# DCDCDC-R2.net
KiCad netlist of a schematic drawn in EAGLE
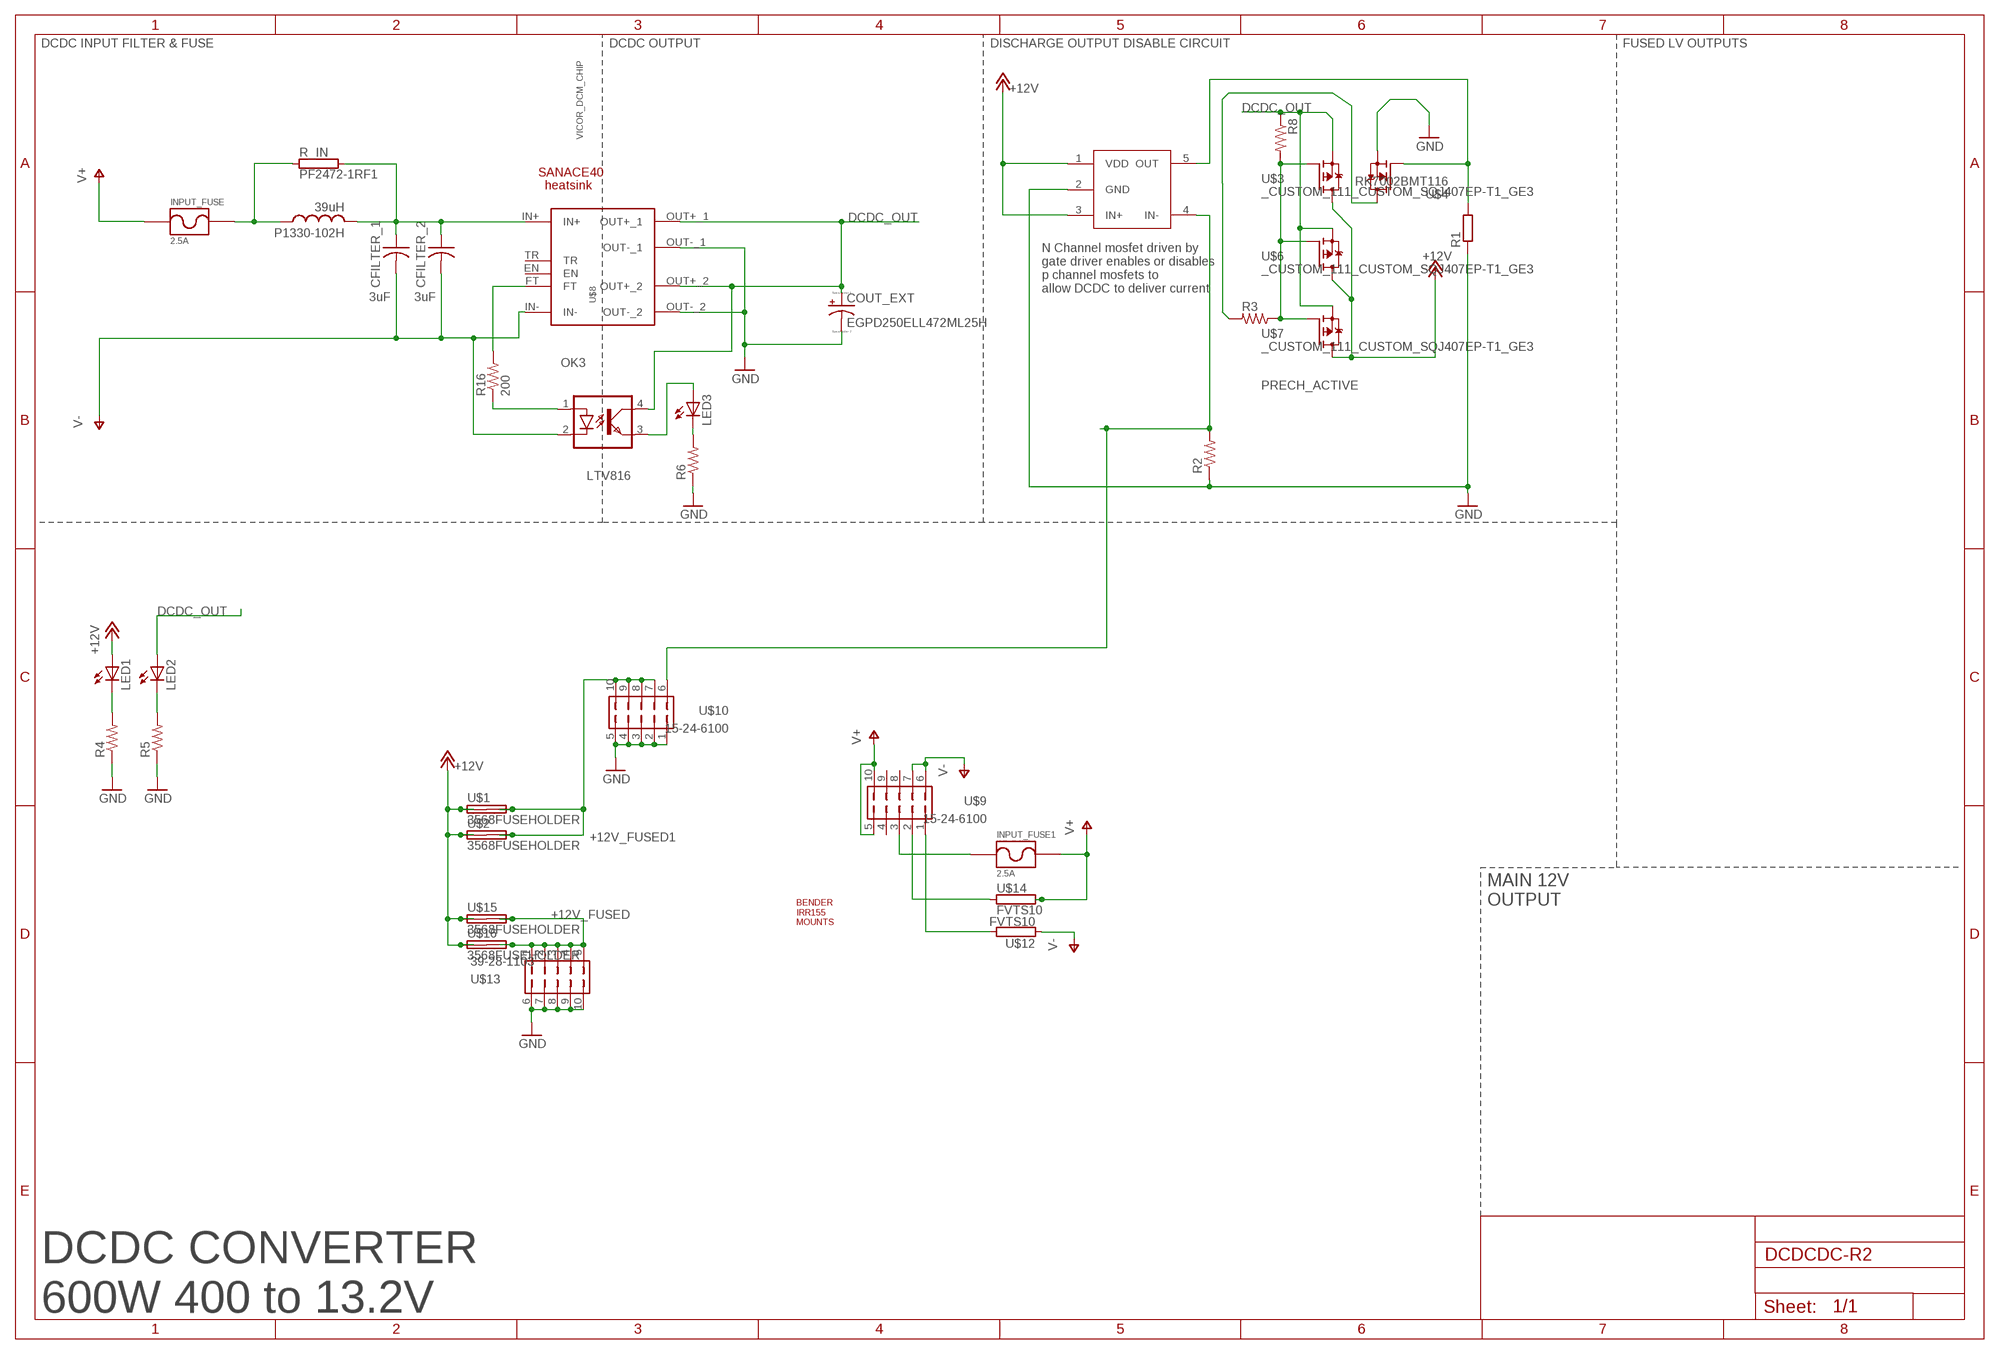
[diagram p0: schematic, sheet 1]

(export (version "E")
  (design (tool "Eeschema 10.0.6"))
  (components
    (comp (ref "CFILTER_1")
      (value "3uF")
      (footprint "eagle-import:CERALINK_FA3")
      (libsource (lib "eagle-import") (part "B58035U5305M062"))
    )
    (comp (ref "CFILTER_2")
      (value "3uF")
      (footprint "eagle-import:CERALINK_FA3")
      (libsource (lib "eagle-import") (part "B58035U5305M062"))
    )
    (comp (ref "COUT_EXT")
      (value "EGPD250ELL472ML25H")
      (footprint "eagle-import:E7,5-16")
      (libsource (lib "eagle-import") (part "CPOL-USE7.5-16"))
    )
    (comp (ref "INPUT_FUSE")
      (value "2.5A")
      (footprint "eagle-import:_CUSTOM_PARTS_LF_885")
      (libsource (lib "eagle-import") (part "_CUSTOM_PARTS_LF_885"))
    )
    (comp (ref "INPUT_FUSE1")
      (value "2.5A")
      (footprint "eagle-import:_CUSTOM_PARTS_LF_885")
      (libsource (lib "eagle-import") (part "_CUSTOM_PARTS_LF_885"))
    )
    (comp (ref "LED1")
      (value "LED3MM")
      (footprint "eagle-import:LED3MM")
      (libsource (lib "eagle-import") (part "LED3MM"))
    )
    (comp (ref "LED2")
      (value "LED3MM")
      (footprint "eagle-import:LED3MM")
      (libsource (lib "eagle-import") (part "LED3MM"))
    )
    (comp (ref "LED3")
      (value "LED3MM")
      (footprint "eagle-import:LED3MM")
      (libsource (lib "eagle-import") (part "LED3MM"))
    )
    (comp (ref "OK3")
      (value "LTV816")
      (footprint "eagle-import:DIL04")
      (libsource (lib "eagle-import") (part "LTV816"))
    )
    (comp (ref "P1330-102H")
      (value "39uH")
      (footprint "eagle-import:L_1510_NONSTANDARD")
      (libsource (lib "eagle-import") (part "SRP1770TA-390M"))
    )
    (comp (ref "R1")
      (value "R-EU_R0805")
      (footprint "eagle-import:R0805")
      (libsource (lib "eagle-import") (part "R-EU_R0805"))
    )
    (comp (ref "R2")
      (value "R-US_R0805")
      (footprint "eagle-import:R0805")
      (libsource (lib "eagle-import") (part "ACC-MB-R0_13324935_R-US_R0805"))
    )
    (comp (ref "R3")
      (value "R-US_R0805")
      (footprint "eagle-import:R0805")
      (libsource (lib "eagle-import") (part "ACC-MB-R0_13324935_R-US_R0805"))
    )
    (comp (ref "R4")
      (value "R-US_R0805")
      (footprint "eagle-import:R0805")
      (libsource (lib "eagle-import") (part "R-US_R0805"))
    )
    (comp (ref "R5")
      (value "R-US_R0805")
      (footprint "eagle-import:R0805")
      (libsource (lib "eagle-import") (part "R-US_R0805"))
    )
    (comp (ref "R6")
      (value "R-US_R0805")
      (footprint "eagle-import:R0805")
      (libsource (lib "eagle-import") (part "R-US_R0805"))
    )
    (comp (ref "R8")
      (value "R-US_R0805")
      (footprint "eagle-import:R0805")
      (libsource (lib "eagle-import") (part "ACC-MB-R0_13324935_R-US_R0805"))
    )
    (comp (ref "R16")
      (value "200")
      (footprint "eagle-import:R2010")
      (libsource (lib "eagle-import") (part "Main_14107900_R-US_R2010"))
    )
    (comp (ref "R_IN")
      (value "PF2472-1RF1")
      (footprint "eagle-import:TO-247-2V")
      (libsource (lib "eagle-import") (part "RMG100-V"))
    )
    (comp (ref "U$1")
      (value "3568FUSEHOLDER")
      (footprint "eagle-import:3568")
      (libsource (lib "eagle-import") (part "3568FUSEHOLDER"))
    )
    (comp (ref "U$2")
      (value "3568FUSEHOLDER")
      (footprint "eagle-import:3568")
      (libsource (lib "eagle-import") (part "3568FUSEHOLDER"))
    )
    (comp (ref "U$3")
      (value "_CUSTOM_111_CUSTOM_SQJ407EP-T1_GE3")
      (footprint "eagle-import:_CUSTOM_111_CUSTOM_TRANS_SIRA90DP-T1-GE3")
      (libsource (lib "eagle-import") (part "_CUSTOM_111_CUSTOM_SQJ407EP-T1_GE3"))
    )
    (comp (ref "U$4")
      (value "RK7002BMT116")
      (footprint "eagle-import:SOT23")
      (libsource (lib "eagle-import") (part "RK7002BMT116"))
    )
    (comp (ref "U$5")
      (value "UCC27511AQDBVRQ1")
      (footprint "eagle-import:SOT23-5L")
      (libsource (lib "eagle-import") (part "UCC27511AQDBVRQ1"))
    )
    (comp (ref "U$6")
      (value "_CUSTOM_111_CUSTOM_SQJ407EP-T1_GE3")
      (footprint "eagle-import:_CUSTOM_111_CUSTOM_TRANS_SIRA90DP-T1-GE3")
      (libsource (lib "eagle-import") (part "_CUSTOM_111_CUSTOM_SQJ407EP-T1_GE3"))
    )
    (comp (ref "U$7")
      (value "_CUSTOM_111_CUSTOM_SQJ407EP-T1_GE3")
      (footprint "eagle-import:_CUSTOM_111_CUSTOM_TRANS_SIRA90DP-T1-GE3")
      (libsource (lib "eagle-import") (part "_CUSTOM_111_CUSTOM_SQJ407EP-T1_GE3"))
    )
    (comp (ref "U$8")
      (value "VICOR_DCM_CHIP")
      (footprint "eagle-import:VICOR_CHIP_HEATSINK")
      (libsource (lib "eagle-import") (part "VICOR_DCM_CHIP"))
    )
    (comp (ref "U$9")
      (value "15-24-6100")
      (footprint "eagle-import:15-24-6100")
      (libsource (lib "eagle-import") (part "15-24-6100"))
    )
    (comp (ref "U$10")
      (value "15-24-6100")
      (footprint "eagle-import:15-24-6100")
      (libsource (lib "eagle-import") (part "15-24-6100"))
    )
    (comp (ref "U$11")
      (value "BENDER_IRR155")
      (footprint "eagle-import:BENDER_IRR155")
      (libsource (lib "eagle-import") (part "BENDER_IRR155"))
    )
    (comp (ref "U$12")
      (value "FVTS10")
      (footprint "eagle-import:FVTS10")
      (libsource (lib "eagle-import") (part "FVTS10"))
    )
    (comp (ref "U$13")
      (value "39-28-1103")
      (footprint "eagle-import:39-28-1103")
      (libsource (lib "eagle-import") (part "39-28-1103"))
    )
    (comp (ref "U$14")
      (value "FVTS10")
      (footprint "eagle-import:FVTS10")
      (libsource (lib "eagle-import") (part "FVTS10"))
    )
    (comp (ref "U$15")
      (value "3568FUSEHOLDER")
      (footprint "eagle-import:3568")
      (libsource (lib "eagle-import") (part "3568FUSEHOLDER"))
    )
    (comp (ref "U$16")
      (value "3568FUSEHOLDER")
      (footprint "eagle-import:3568")
      (libsource (lib "eagle-import") (part "3568FUSEHOLDER"))
    )
    (comp (ref "U$17")
      (value "VICOR_HEATSINK_19MMLONG")
      (footprint "eagle-import:VICOR_HEATSINK_19MM_LONG")
      (libsource (lib "eagle-import") (part "VICOR_HEATSINK_19MMLONG"))
    )
    (comp (ref "U$18")
      (value "SANACE40")
      (footprint "eagle-import:SANACE40")
      (libsource (lib "eagle-import") (part "SANACE40"))
    )
  )
  (nets
    (net (code "1") (name "+12V") (class "Default")
      (node (ref "LED1") (pin "A") (pinfunction "A_A") (pintype "passive"))
      (node (ref "U$1") (pin "L1") (pinfunction "1A_L1") (pintype "passive"))
      (node (ref "U$1") (pin "L2") (pinfunction "1B_L2") (pintype "passive"))
      (node (ref "U$15") (pin "L1") (pinfunction "1A_L1") (pintype "passive"))
      (node (ref "U$15") (pin "L2") (pinfunction "1B_L2") (pintype "passive"))
      (node (ref "U$16") (pin "L1") (pinfunction "1A_L1") (pintype "passive"))
      (node (ref "U$16") (pin "L2") (pinfunction "1B_L2") (pintype "passive"))
      (node (ref "U$2") (pin "L1") (pinfunction "1A_L1") (pintype "passive"))
      (node (ref "U$2") (pin "L2") (pinfunction "1B_L2") (pintype "passive"))
      (node (ref "U$3") (pin "5") (pinfunction "D_5") (pintype "passive"))
      (node (ref "U$5") (pin "1") (pinfunction "VDD_1") (pintype "bidirectional"))
      (node (ref "U$5") (pin "3") (pinfunction "IN+_3") (pintype "bidirectional"))
      (node (ref "U$6") (pin "5") (pinfunction "D_5") (pintype "passive"))
      (node (ref "U$7") (pin "5") (pinfunction "D_5") (pintype "passive"))
    )
    (net (code "2") (name "/+12V_FUSED") (class "Default")
      (node (ref "U$13") (pin "1") (pinfunction "1_1") (pintype "passive"))
      (node (ref "U$13") (pin "2") (pinfunction "2_2") (pintype "passive"))
      (node (ref "U$13") (pin "3") (pinfunction "3_3") (pintype "passive"))
      (node (ref "U$13") (pin "4") (pinfunction "4_4") (pintype "passive"))
      (node (ref "U$13") (pin "5") (pinfunction "5_5") (pintype "passive"))
      (node (ref "U$15") (pin "R1") (pinfunction "2A_R1") (pintype "passive"))
      (node (ref "U$15") (pin "R2") (pinfunction "2B_R2") (pintype "passive"))
      (node (ref "U$16") (pin "R1") (pinfunction "2A_R1") (pintype "passive"))
      (node (ref "U$16") (pin "R2") (pinfunction "2B_R2") (pintype "passive"))
    )
    (net (code "3") (name "/+12V_FUSED1") (class "Default")
      (node (ref "U$1") (pin "R1") (pinfunction "2A_R1") (pintype "passive"))
      (node (ref "U$1") (pin "R2") (pinfunction "2B_R2") (pintype "passive"))
      (node (ref "U$10") (pin "10") (pinfunction "10_10") (pintype "passive"))
      (node (ref "U$10") (pin "7") (pinfunction "7_7") (pintype "passive"))
      (node (ref "U$10") (pin "8") (pinfunction "8_8") (pintype "passive"))
      (node (ref "U$10") (pin "9") (pinfunction "9_9") (pintype "passive"))
      (node (ref "U$2") (pin "R1") (pinfunction "2A_R1") (pintype "passive"))
      (node (ref "U$2") (pin "R2") (pinfunction "2B_R2") (pintype "passive"))
    )
    (net (code "4") (name "/DCDC_OUT") (class "Default")
      (node (ref "COUT_EXT") (pin "+") (pinfunction "+_+") (pintype "passive"))
      (node (ref "LED2") (pin "A") (pinfunction "A_A") (pintype "passive"))
      (node (ref "OK3") (pin "4") (pinfunction "COL_4") (pintype "passive"))
      (node (ref "R8") (pin "1") (pinfunction "1_1") (pintype "passive"))
      (node (ref "U$3") (pin "1") (pinfunction "S_1") (pintype "passive"))
      (node (ref "U$3") (pin "2") (pinfunction "S_2") (pintype "passive"))
      (node (ref "U$3") (pin "3") (pinfunction "S_3") (pintype "passive"))
      (node (ref "U$6") (pin "1") (pinfunction "S_1") (pintype "passive"))
      (node (ref "U$6") (pin "2") (pinfunction "S_2") (pintype "passive"))
      (node (ref "U$6") (pin "3") (pinfunction "S_3") (pintype "passive"))
      (node (ref "U$7") (pin "1") (pinfunction "S_1") (pintype "passive"))
      (node (ref "U$7") (pin "2") (pinfunction "S_2") (pintype "passive"))
      (node (ref "U$7") (pin "3") (pinfunction "S_3") (pintype "passive"))
      (node (ref "U$8") (pin "OUT+_1") (pinfunction "OUT+_1_OUT+_1") (pintype "bidirectional"))
      (node (ref "U$8") (pin "OUT+_2") (pinfunction "OUT+_2_OUT+_2") (pintype "bidirectional"))
    )
    (net (code "5") (name "/PRECH_ACTIVE") (class "Default")
      (node (ref "R2") (pin "2") (pinfunction "2_2") (pintype "passive"))
      (node (ref "U$10") (pin "6") (pinfunction "6_6") (pintype "passive"))
      (node (ref "U$5") (pin "4") (pinfunction "IN-_4") (pintype "bidirectional"))
    )
    (net (code "6") (name "GND") (class "Default")
      (node (ref "COUT_EXT") (pin "-") (pinfunction "-_-") (pintype "passive"))
      (node (ref "R1") (pin "1") (pinfunction "1_1") (pintype "passive"))
      (node (ref "R2") (pin "1") (pinfunction "1_1") (pintype "passive"))
      (node (ref "R4") (pin "1") (pinfunction "1_1") (pintype "passive"))
      (node (ref "R5") (pin "1") (pinfunction "1_1") (pintype "passive"))
      (node (ref "R6") (pin "1") (pinfunction "1_1") (pintype "passive"))
      (node (ref "U$10") (pin "1") (pinfunction "1_1") (pintype "passive"))
      (node (ref "U$10") (pin "2") (pinfunction "2_2") (pintype "passive"))
      (node (ref "U$10") (pin "3") (pinfunction "3_3") (pintype "passive"))
      (node (ref "U$10") (pin "4") (pinfunction "4_4") (pintype "passive"))
      (node (ref "U$10") (pin "5") (pinfunction "5_5") (pintype "passive"))
      (node (ref "U$13") (pin "10") (pinfunction "10_10") (pintype "passive"))
      (node (ref "U$13") (pin "6") (pinfunction "6_6") (pintype "passive"))
      (node (ref "U$13") (pin "7") (pinfunction "7_7") (pintype "passive"))
      (node (ref "U$13") (pin "8") (pinfunction "8_8") (pintype "passive"))
      (node (ref "U$13") (pin "9") (pinfunction "9_9") (pintype "passive"))
      (node (ref "U$4") (pin "2") (pinfunction "S_2") (pintype "passive"))
      (node (ref "U$5") (pin "2") (pinfunction "GND_2") (pintype "bidirectional"))
      (node (ref "U$8") (pin "OUT-_1") (pinfunction "OUT-_1_OUT-_1") (pintype "bidirectional"))
      (node (ref "U$8") (pin "OUT-_2") (pinfunction "OUT-_2_OUT-_2") (pintype "bidirectional"))
    )
    (net (code "7") (name "Net-(CFILTER_1-1)") (class "Default")
      (node (ref "CFILTER_1") (pin "P$1") (pinfunction "1_P$1") (pintype "passive"))
      (node (ref "CFILTER_2") (pin "P$1") (pinfunction "1_P$1") (pintype "passive"))
      (node (ref "P1330-102H") (pin "P$2") (pinfunction "2_P$2") (pintype "passive"))
      (node (ref "R_IN") (pin "2") (pinfunction "2_2") (pintype "passive"))
      (node (ref "U$8") (pin "IN+") (pinfunction "IN+_IN+") (pintype "bidirectional"))
    )
    (net (code "8") (name "Net-(INPUT_FUSE1-PadP$1)") (class "Default")
      (node (ref "INPUT_FUSE1") (pin "P$1") (pinfunction "P$1_P$1") (pintype "bidirectional"))
      (node (ref "U$9") (pin "3") (pinfunction "3_3") (pintype "passive"))
    )
    (net (code "9") (name "Net-(LED1-C)") (class "Default")
      (node (ref "LED1") (pin "K") (pinfunction "C_K") (pintype "passive"))
      (node (ref "R4") (pin "2") (pinfunction "2_2") (pintype "passive"))
    )
    (net (code "10") (name "Net-(LED2-C)") (class "Default")
      (node (ref "LED2") (pin "K") (pinfunction "C_K") (pintype "passive"))
      (node (ref "R5") (pin "2") (pinfunction "2_2") (pintype "passive"))
    )
    (net (code "11") (name "Net-(LED3-C)") (class "Default")
      (node (ref "LED3") (pin "K") (pinfunction "C_K") (pintype "passive"))
      (node (ref "R6") (pin "2") (pinfunction "2_2") (pintype "passive"))
    )
    (net (code "12") (name "Net-(OK3-A)") (class "Default")
      (node (ref "OK3") (pin "1") (pinfunction "A_1") (pintype "passive"))
      (node (ref "R16") (pin "1") (pinfunction "1_1") (pintype "passive"))
    )
    (net (code "13") (name "Net-(OK3-EMIT)") (class "Default")
      (node (ref "LED3") (pin "A") (pinfunction "A_A") (pintype "passive"))
      (node (ref "OK3") (pin "3") (pinfunction "EMIT_3") (pintype "passive"))
    )
    (net (code "14") (name "Net-(P1330-102H-1)") (class "Default")
      (node (ref "INPUT_FUSE") (pin "P$2") (pinfunction "P$2_P$2") (pintype "bidirectional"))
      (node (ref "P1330-102H") (pin "P$1") (pinfunction "1_P$1") (pintype "passive"))
      (node (ref "R_IN") (pin "1") (pinfunction "1_1") (pintype "passive"))
    )
    (net (code "15") (name "Net-(R16-Pad2)") (class "Default")
      (node (ref "R16") (pin "2") (pinfunction "2_2") (pintype "passive"))
      (node (ref "U$8") (pin "FT") (pinfunction "FT_FT") (pintype "bidirectional"))
    )
    (net (code "16") (name "Net-(U$3-G)") (class "Default")
      (node (ref "R3") (pin "1") (pinfunction "1_1") (pintype "passive"))
      (node (ref "R8") (pin "2") (pinfunction "2_2") (pintype "passive"))
      (node (ref "U$3") (pin "4") (pinfunction "G_4") (pintype "passive"))
      (node (ref "U$6") (pin "4") (pinfunction "G_4") (pintype "passive"))
      (node (ref "U$7") (pin "4") (pinfunction "G_4") (pintype "passive"))
    )
    (net (code "17") (name "Net-(U$4-D)") (class "Default")
      (node (ref "R3") (pin "2") (pinfunction "2_2") (pintype "passive"))
      (node (ref "U$4") (pin "3") (pinfunction "D_3") (pintype "passive"))
    )
    (net (code "18") (name "Net-(U$4-G)") (class "Default")
      (node (ref "R1") (pin "2") (pinfunction "2_2") (pintype "passive"))
      (node (ref "U$4") (pin "1") (pinfunction "G_1") (pintype "passive"))
      (node (ref "U$5") (pin "5") (pinfunction "OUT_5") (pintype "bidirectional"))
    )
    (net (code "19") (name "Net-(U$12-2)") (class "Default")
      (node (ref "U$12") (pin "P$2") (pinfunction "2_P$2") (pintype "passive"))
      (node (ref "U$9") (pin "1") (pinfunction "1_1") (pintype "passive"))
    )
    (net (code "20") (name "Net-(U$14-1)") (class "Default")
      (node (ref "U$14") (pin "P$1") (pinfunction "1_P$1") (pintype "passive"))
      (node (ref "U$9") (pin "2") (pinfunction "2_2") (pintype "passive"))
    )
    (net (code "21") (name "V+") (class "Default")
      (node (ref "INPUT_FUSE") (pin "P$1") (pinfunction "P$1_P$1") (pintype "bidirectional"))
      (node (ref "INPUT_FUSE1") (pin "P$2") (pinfunction "P$2_P$2") (pintype "bidirectional"))
      (node (ref "U$14") (pin "P$2") (pinfunction "2_P$2") (pintype "passive"))
      (node (ref "U$9") (pin "10") (pinfunction "10_10") (pintype "passive"))
      (node (ref "U$9") (pin "5") (pinfunction "5_5") (pintype "passive"))
    )
    (net (code "22") (name "V-") (class "Default")
      (node (ref "CFILTER_1") (pin "P$2") (pinfunction "2_P$2") (pintype "passive"))
      (node (ref "CFILTER_2") (pin "P$2") (pinfunction "2_P$2") (pintype "passive"))
      (node (ref "OK3") (pin "2") (pinfunction "C_2") (pintype "passive"))
      (node (ref "U$12") (pin "P$1") (pinfunction "1_P$1") (pintype "passive"))
      (node (ref "U$8") (pin "IN-") (pinfunction "IN-_IN-") (pintype "bidirectional"))
      (node (ref "U$9") (pin "6") (pinfunction "6_6") (pintype "passive"))
      (node (ref "U$9") (pin "7") (pinfunction "7_7") (pintype "passive"))
    )
    (net (code "23") (name "unconnected-(U$8-PadEN)") (class "Default")
      (node (ref "U$8") (pin "EN") (pinfunction "EN_EN") (pintype "bidirectional"))
    )
    (net (code "24") (name "unconnected-(U$8-PadTR)") (class "Default")
      (node (ref "U$8") (pin "TR") (pinfunction "TR_TR") (pintype "bidirectional"))
    )
    (net (code "25") (name "unconnected-(U$9-Pad4)") (class "Default")
      (node (ref "U$9") (pin "4") (pinfunction "4_4") (pintype "passive"))
    )
    (net (code "26") (name "unconnected-(U$9-Pad8)") (class "Default")
      (node (ref "U$9") (pin "8") (pinfunction "8_8") (pintype "passive"))
    )
    (net (code "27") (name "unconnected-(U$9-Pad9)") (class "Default")
      (node (ref "U$9") (pin "9") (pinfunction "9_9") (pintype "passive"))
    )
  )
)
